# Fysetc_F6_TMC-Shield_HV.net
KiCad netlist of a schematic drawn in EAGLE
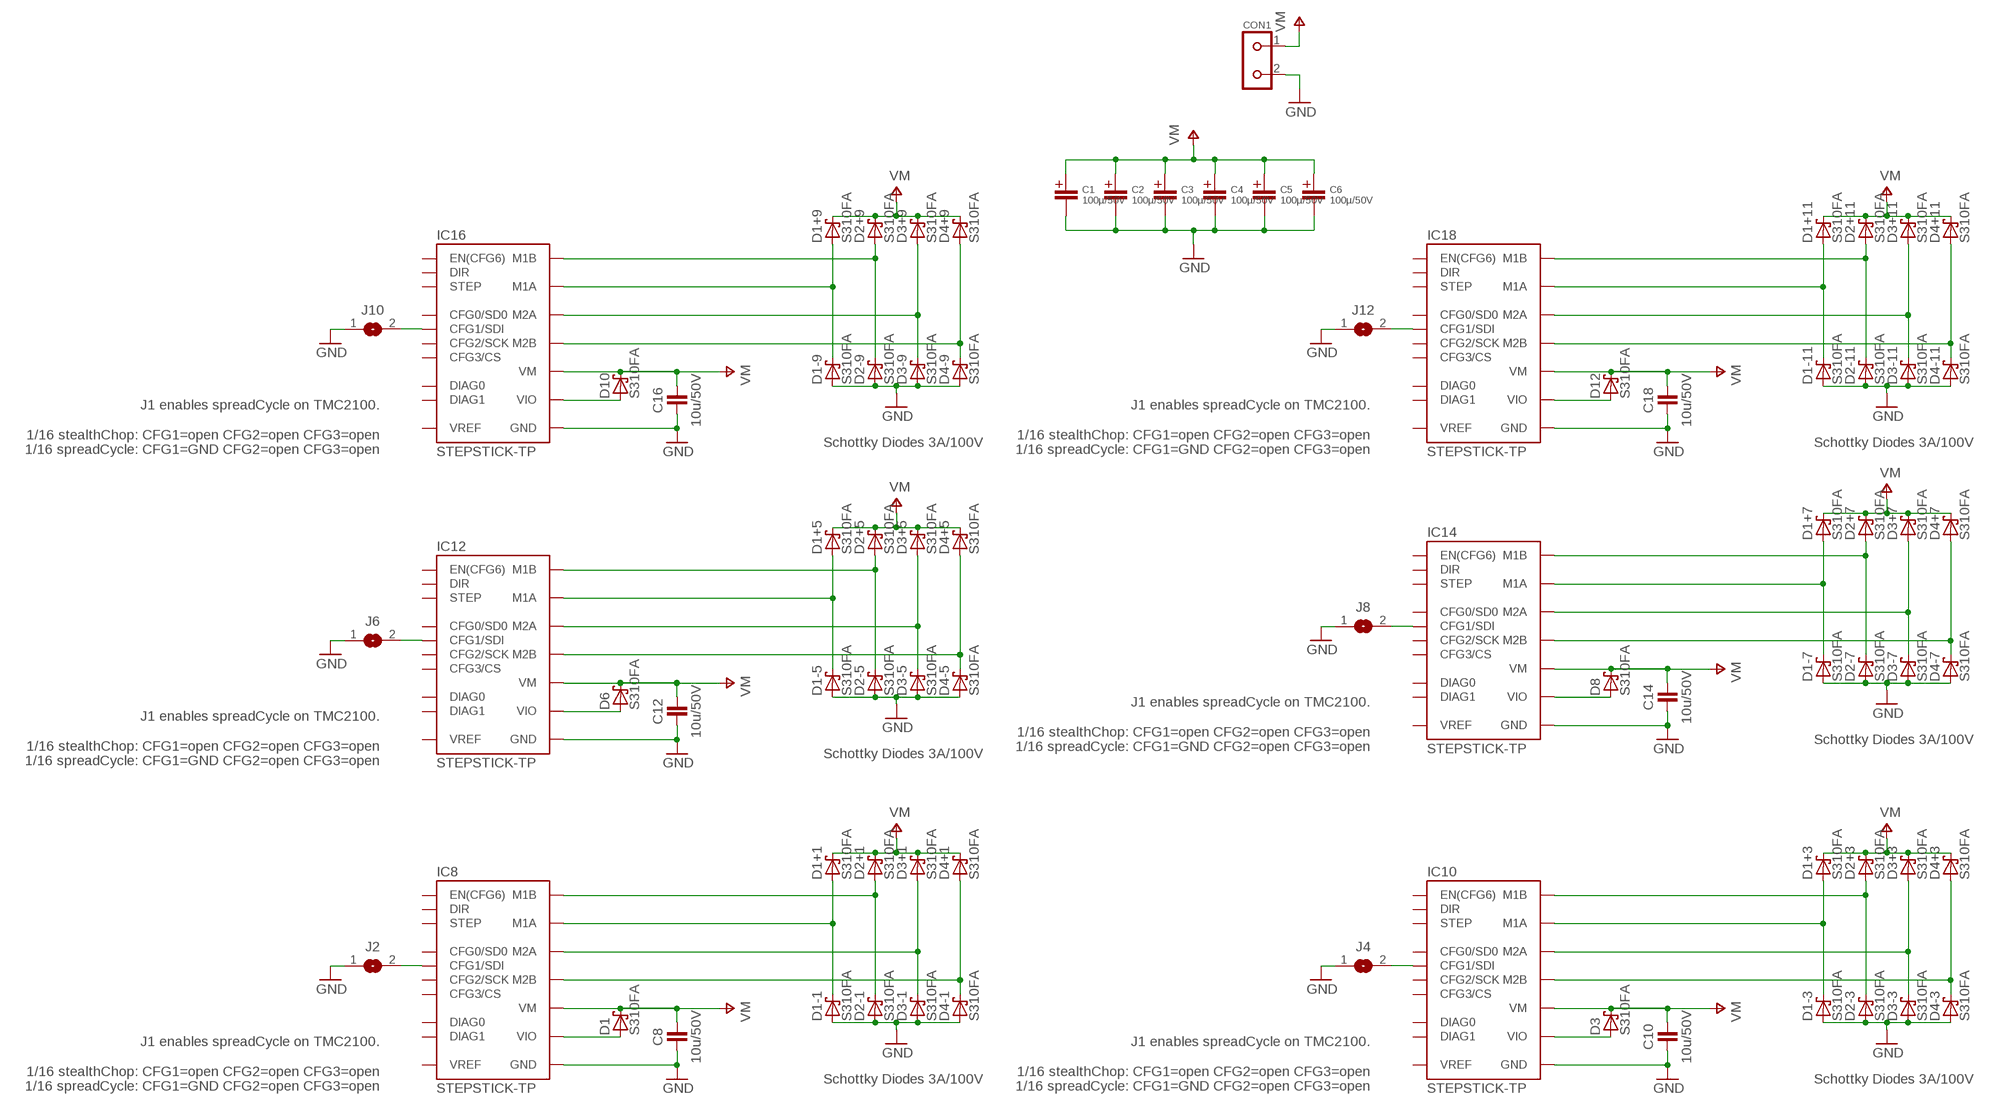
[diagram p0: schematic, sheet 1]

(export (version "E")
  (design (tool "Eeschema 10.0.6"))
  (components
    (comp (ref "C1")
      (value "100µ/50V")
      (footprint "eagle-import:C+_3.5_8")
      (libsource (lib "eagle-import") (part "C+3.5/8"))
    )
    (comp (ref "C2")
      (value "100µ/50V")
      (footprint "eagle-import:C+_3.5_8")
      (libsource (lib "eagle-import") (part "C+3.5/8"))
    )
    (comp (ref "C3")
      (value "100µ/50V")
      (footprint "eagle-import:C+_3.5_8")
      (libsource (lib "eagle-import") (part "C+3.5/8"))
    )
    (comp (ref "C4")
      (value "100µ/50V")
      (footprint "eagle-import:C+_3.5_8")
      (libsource (lib "eagle-import") (part "C+3.5/8"))
    )
    (comp (ref "C5")
      (value "100µ/50V")
      (footprint "eagle-import:C+_3.5_8")
      (libsource (lib "eagle-import") (part "C+3.5/8"))
    )
    (comp (ref "C6")
      (value "100µ/50V")
      (footprint "eagle-import:C+_3.5_8")
      (libsource (lib "eagle-import") (part "C+3.5/8"))
    )
    (comp (ref "C8")
      (value "10u/50V")
      (footprint "eagle-import:C1210")
      (libsource (lib "eagle-import") (part "CAPACITOR-1210"))
    )
    (comp (ref "C10")
      (value "10u/50V")
      (footprint "eagle-import:C1210")
      (libsource (lib "eagle-import") (part "CAPACITOR-1210"))
    )
    (comp (ref "C12")
      (value "10u/50V")
      (footprint "eagle-import:C1210")
      (libsource (lib "eagle-import") (part "CAPACITOR-1210"))
    )
    (comp (ref "C14")
      (value "10u/50V")
      (footprint "eagle-import:C1210")
      (libsource (lib "eagle-import") (part "CAPACITOR-1210"))
    )
    (comp (ref "C16")
      (value "10u/50V")
      (footprint "eagle-import:C1210")
      (libsource (lib "eagle-import") (part "CAPACITOR-1210"))
    )
    (comp (ref "C18")
      (value "10u/50V")
      (footprint "eagle-import:C1210")
      (libsource (lib "eagle-import") (part "CAPACITOR-1210"))
    )
    (comp (ref "CON1")
      (value "KL2691311500002")
      (footprint "eagle-import:KL2-691311500002")
      (libsource (lib "eagle-import") (part "KL2691311500002"))
    )
    (comp (ref "D1")
      (value "S310FA")
      (footprint "eagle-import:SOD123")
      (libsource (lib "eagle-import") (part "D_SCHOTTKY-SOD123"))
    )
    (comp (ref "D1+1")
      (value "S310FA")
      (footprint "eagle-import:SOD123")
      (libsource (lib "eagle-import") (part "D_SCHOTTKY-SOD123"))
    )
    (comp (ref "D1+3")
      (value "S310FA")
      (footprint "eagle-import:SOD123")
      (libsource (lib "eagle-import") (part "D_SCHOTTKY-SOD123"))
    )
    (comp (ref "D1+5")
      (value "S310FA")
      (footprint "eagle-import:SOD123")
      (libsource (lib "eagle-import") (part "D_SCHOTTKY-SOD123"))
    )
    (comp (ref "D1+7")
      (value "S310FA")
      (footprint "eagle-import:SOD123")
      (libsource (lib "eagle-import") (part "D_SCHOTTKY-SOD123"))
    )
    (comp (ref "D1+9")
      (value "S310FA")
      (footprint "eagle-import:SOD123")
      (libsource (lib "eagle-import") (part "D_SCHOTTKY-SOD123"))
    )
    (comp (ref "D1+11")
      (value "S310FA")
      (footprint "eagle-import:SOD123")
      (libsource (lib "eagle-import") (part "D_SCHOTTKY-SOD123"))
    )
    (comp (ref "D1-1")
      (value "S310FA")
      (footprint "eagle-import:SOD123")
      (libsource (lib "eagle-import") (part "D_SCHOTTKY-SOD123"))
    )
    (comp (ref "D1-3")
      (value "S310FA")
      (footprint "eagle-import:SOD123")
      (libsource (lib "eagle-import") (part "D_SCHOTTKY-SOD123"))
    )
    (comp (ref "D1-5")
      (value "S310FA")
      (footprint "eagle-import:SOD123")
      (libsource (lib "eagle-import") (part "D_SCHOTTKY-SOD123"))
    )
    (comp (ref "D1-7")
      (value "S310FA")
      (footprint "eagle-import:SOD123")
      (libsource (lib "eagle-import") (part "D_SCHOTTKY-SOD123"))
    )
    (comp (ref "D1-9")
      (value "S310FA")
      (footprint "eagle-import:SOD123")
      (libsource (lib "eagle-import") (part "D_SCHOTTKY-SOD123"))
    )
    (comp (ref "D1-11")
      (value "S310FA")
      (footprint "eagle-import:SOD123")
      (libsource (lib "eagle-import") (part "D_SCHOTTKY-SOD123"))
    )
    (comp (ref "D2+1")
      (value "S310FA")
      (footprint "eagle-import:SOD123")
      (libsource (lib "eagle-import") (part "D_SCHOTTKY-SOD123"))
    )
    (comp (ref "D2+3")
      (value "S310FA")
      (footprint "eagle-import:SOD123")
      (libsource (lib "eagle-import") (part "D_SCHOTTKY-SOD123"))
    )
    (comp (ref "D2+5")
      (value "S310FA")
      (footprint "eagle-import:SOD123")
      (libsource (lib "eagle-import") (part "D_SCHOTTKY-SOD123"))
    )
    (comp (ref "D2+7")
      (value "S310FA")
      (footprint "eagle-import:SOD123")
      (libsource (lib "eagle-import") (part "D_SCHOTTKY-SOD123"))
    )
    (comp (ref "D2+9")
      (value "S310FA")
      (footprint "eagle-import:SOD123")
      (libsource (lib "eagle-import") (part "D_SCHOTTKY-SOD123"))
    )
    (comp (ref "D2+11")
      (value "S310FA")
      (footprint "eagle-import:SOD123")
      (libsource (lib "eagle-import") (part "D_SCHOTTKY-SOD123"))
    )
    (comp (ref "D2-1")
      (value "S310FA")
      (footprint "eagle-import:SOD123")
      (libsource (lib "eagle-import") (part "D_SCHOTTKY-SOD123"))
    )
    (comp (ref "D2-3")
      (value "S310FA")
      (footprint "eagle-import:SOD123")
      (libsource (lib "eagle-import") (part "D_SCHOTTKY-SOD123"))
    )
    (comp (ref "D2-5")
      (value "S310FA")
      (footprint "eagle-import:SOD123")
      (libsource (lib "eagle-import") (part "D_SCHOTTKY-SOD123"))
    )
    (comp (ref "D2-7")
      (value "S310FA")
      (footprint "eagle-import:SOD123")
      (libsource (lib "eagle-import") (part "D_SCHOTTKY-SOD123"))
    )
    (comp (ref "D2-9")
      (value "S310FA")
      (footprint "eagle-import:SOD123")
      (libsource (lib "eagle-import") (part "D_SCHOTTKY-SOD123"))
    )
    (comp (ref "D2-11")
      (value "S310FA")
      (footprint "eagle-import:SOD123")
      (libsource (lib "eagle-import") (part "D_SCHOTTKY-SOD123"))
    )
    (comp (ref "D3")
      (value "S310FA")
      (footprint "eagle-import:SOD123")
      (libsource (lib "eagle-import") (part "D_SCHOTTKY-SOD123"))
    )
    (comp (ref "D3+1")
      (value "S310FA")
      (footprint "eagle-import:SOD123")
      (libsource (lib "eagle-import") (part "D_SCHOTTKY-SOD123"))
    )
    (comp (ref "D3+3")
      (value "S310FA")
      (footprint "eagle-import:SOD123")
      (libsource (lib "eagle-import") (part "D_SCHOTTKY-SOD123"))
    )
    (comp (ref "D3+5")
      (value "S310FA")
      (footprint "eagle-import:SOD123")
      (libsource (lib "eagle-import") (part "D_SCHOTTKY-SOD123"))
    )
    (comp (ref "D3+7")
      (value "S310FA")
      (footprint "eagle-import:SOD123")
      (libsource (lib "eagle-import") (part "D_SCHOTTKY-SOD123"))
    )
    (comp (ref "D3+9")
      (value "S310FA")
      (footprint "eagle-import:SOD123")
      (libsource (lib "eagle-import") (part "D_SCHOTTKY-SOD123"))
    )
    (comp (ref "D3+11")
      (value "S310FA")
      (footprint "eagle-import:SOD123")
      (libsource (lib "eagle-import") (part "D_SCHOTTKY-SOD123"))
    )
    (comp (ref "D3-1")
      (value "S310FA")
      (footprint "eagle-import:SOD123")
      (libsource (lib "eagle-import") (part "D_SCHOTTKY-SOD123"))
    )
    (comp (ref "D3-3")
      (value "S310FA")
      (footprint "eagle-import:SOD123")
      (libsource (lib "eagle-import") (part "D_SCHOTTKY-SOD123"))
    )
    (comp (ref "D3-5")
      (value "S310FA")
      (footprint "eagle-import:SOD123")
      (libsource (lib "eagle-import") (part "D_SCHOTTKY-SOD123"))
    )
    (comp (ref "D3-7")
      (value "S310FA")
      (footprint "eagle-import:SOD123")
      (libsource (lib "eagle-import") (part "D_SCHOTTKY-SOD123"))
    )
    (comp (ref "D3-9")
      (value "S310FA")
      (footprint "eagle-import:SOD123")
      (libsource (lib "eagle-import") (part "D_SCHOTTKY-SOD123"))
    )
    (comp (ref "D3-11")
      (value "S310FA")
      (footprint "eagle-import:SOD123")
      (libsource (lib "eagle-import") (part "D_SCHOTTKY-SOD123"))
    )
    (comp (ref "D4+1")
      (value "S310FA")
      (footprint "eagle-import:SOD123")
      (libsource (lib "eagle-import") (part "D_SCHOTTKY-SOD123"))
    )
    (comp (ref "D4+3")
      (value "S310FA")
      (footprint "eagle-import:SOD123")
      (libsource (lib "eagle-import") (part "D_SCHOTTKY-SOD123"))
    )
    (comp (ref "D4+5")
      (value "S310FA")
      (footprint "eagle-import:SOD123")
      (libsource (lib "eagle-import") (part "D_SCHOTTKY-SOD123"))
    )
    (comp (ref "D4+7")
      (value "S310FA")
      (footprint "eagle-import:SOD123")
      (libsource (lib "eagle-import") (part "D_SCHOTTKY-SOD123"))
    )
    (comp (ref "D4+9")
      (value "S310FA")
      (footprint "eagle-import:SOD123")
      (libsource (lib "eagle-import") (part "D_SCHOTTKY-SOD123"))
    )
    (comp (ref "D4+11")
      (value "S310FA")
      (footprint "eagle-import:SOD123")
      (libsource (lib "eagle-import") (part "D_SCHOTTKY-SOD123"))
    )
    (comp (ref "D4-1")
      (value "S310FA")
      (footprint "eagle-import:SOD123")
      (libsource (lib "eagle-import") (part "D_SCHOTTKY-SOD123"))
    )
    (comp (ref "D4-3")
      (value "S310FA")
      (footprint "eagle-import:SOD123")
      (libsource (lib "eagle-import") (part "D_SCHOTTKY-SOD123"))
    )
    (comp (ref "D4-5")
      (value "S310FA")
      (footprint "eagle-import:SOD123")
      (libsource (lib "eagle-import") (part "D_SCHOTTKY-SOD123"))
    )
    (comp (ref "D4-7")
      (value "S310FA")
      (footprint "eagle-import:SOD123")
      (libsource (lib "eagle-import") (part "D_SCHOTTKY-SOD123"))
    )
    (comp (ref "D4-9")
      (value "S310FA")
      (footprint "eagle-import:SOD123")
      (libsource (lib "eagle-import") (part "D_SCHOTTKY-SOD123"))
    )
    (comp (ref "D4-11")
      (value "S310FA")
      (footprint "eagle-import:SOD123")
      (libsource (lib "eagle-import") (part "D_SCHOTTKY-SOD123"))
    )
    (comp (ref "D6")
      (value "S310FA")
      (footprint "eagle-import:SOD123")
      (libsource (lib "eagle-import") (part "D_SCHOTTKY-SOD123"))
    )
    (comp (ref "D8")
      (value "S310FA")
      (footprint "eagle-import:SOD123")
      (libsource (lib "eagle-import") (part "D_SCHOTTKY-SOD123"))
    )
    (comp (ref "D10")
      (value "S310FA")
      (footprint "eagle-import:SOD123")
      (libsource (lib "eagle-import") (part "D_SCHOTTKY-SOD123"))
    )
    (comp (ref "D12")
      (value "S310FA")
      (footprint "eagle-import:SOD123")
      (libsource (lib "eagle-import") (part "D_SCHOTTKY-SOD123"))
    )
    (comp (ref "IC8")
      (value "STEPSTICK-TP")
      (footprint "eagle-import:STEPSTICK_TP")
      (libsource (lib "eagle-import") (part "STEPSTICK-TP"))
    )
    (comp (ref "IC10")
      (value "STEPSTICK-TP")
      (footprint "eagle-import:STEPSTICK_TP")
      (libsource (lib "eagle-import") (part "STEPSTICK-TP"))
    )
    (comp (ref "IC12")
      (value "STEPSTICK-TP")
      (footprint "eagle-import:STEPSTICK_TP")
      (libsource (lib "eagle-import") (part "STEPSTICK-TP"))
    )
    (comp (ref "IC14")
      (value "STEPSTICK-TP")
      (footprint "eagle-import:STEPSTICK_TP")
      (libsource (lib "eagle-import") (part "STEPSTICK-TP"))
    )
    (comp (ref "IC16")
      (value "STEPSTICK-TP")
      (footprint "eagle-import:STEPSTICK_TP")
      (libsource (lib "eagle-import") (part "STEPSTICK-TP"))
    )
    (comp (ref "IC18")
      (value "STEPSTICK-TP")
      (footprint "eagle-import:STEPSTICK_TP")
      (libsource (lib "eagle-import") (part "STEPSTICK-TP"))
    )
    (comp (ref "J2")
      (value "JUMPER2-0603-NC")
      (footprint "eagle-import:JUMPER2-0603_NC")
      (libsource (lib "eagle-import") (part "JUMPER2-0603-NC"))
    )
    (comp (ref "J4")
      (value "JUMPER2-0603-NC")
      (footprint "eagle-import:JUMPER2-0603_NC")
      (libsource (lib "eagle-import") (part "JUMPER2-0603-NC"))
    )
    (comp (ref "J6")
      (value "JUMPER2-0603-NC")
      (footprint "eagle-import:JUMPER2-0603_NC")
      (libsource (lib "eagle-import") (part "JUMPER2-0603-NC"))
    )
    (comp (ref "J8")
      (value "JUMPER2-0603-NC")
      (footprint "eagle-import:JUMPER2-0603_NC")
      (libsource (lib "eagle-import") (part "JUMPER2-0603-NC"))
    )
    (comp (ref "J10")
      (value "JUMPER2-0603-NC")
      (footprint "eagle-import:JUMPER2-0603_NC")
      (libsource (lib "eagle-import") (part "JUMPER2-0603-NC"))
    )
    (comp (ref "J12")
      (value "JUMPER2-0603-NC")
      (footprint "eagle-import:JUMPER2-0603_NC")
      (libsource (lib "eagle-import") (part "JUMPER2-0603-NC"))
    )
  )
  (nets
    (net (code "1") (name "GND") (class "Default")
      (node (ref "C1") (pin "-") (pinfunction "-_-") (pintype "passive"))
      (node (ref "C10") (pin "1") (pinfunction "1_1") (pintype "passive"))
      (node (ref "C12") (pin "1") (pinfunction "1_1") (pintype "passive"))
      (node (ref "C14") (pin "1") (pinfunction "1_1") (pintype "passive"))
      (node (ref "C16") (pin "1") (pinfunction "1_1") (pintype "passive"))
      (node (ref "C18") (pin "1") (pinfunction "1_1") (pintype "passive"))
      (node (ref "C2") (pin "-") (pinfunction "-_-") (pintype "passive"))
      (node (ref "C3") (pin "-") (pinfunction "-_-") (pintype "passive"))
      (node (ref "C4") (pin "-") (pinfunction "-_-") (pintype "passive"))
      (node (ref "C5") (pin "-") (pinfunction "-_-") (pintype "passive"))
      (node (ref "C6") (pin "-") (pinfunction "-_-") (pintype "passive"))
      (node (ref "C8") (pin "1") (pinfunction "1_1") (pintype "passive"))
      (node (ref "CON1") (pin "2") (pinfunction "2_2") (pintype "passive"))
      (node (ref "D1-1") (pin "A") (pinfunction "A_A") (pintype "passive"))
      (node (ref "D1-11") (pin "A") (pinfunction "A_A") (pintype "passive"))
      (node (ref "D1-3") (pin "A") (pinfunction "A_A") (pintype "passive"))
      (node (ref "D1-5") (pin "A") (pinfunction "A_A") (pintype "passive"))
      (node (ref "D1-7") (pin "A") (pinfunction "A_A") (pintype "passive"))
      (node (ref "D1-9") (pin "A") (pinfunction "A_A") (pintype "passive"))
      (node (ref "D2-1") (pin "A") (pinfunction "A_A") (pintype "passive"))
      (node (ref "D2-11") (pin "A") (pinfunction "A_A") (pintype "passive"))
      (node (ref "D2-3") (pin "A") (pinfunction "A_A") (pintype "passive"))
      (node (ref "D2-5") (pin "A") (pinfunction "A_A") (pintype "passive"))
      (node (ref "D2-7") (pin "A") (pinfunction "A_A") (pintype "passive"))
      (node (ref "D2-9") (pin "A") (pinfunction "A_A") (pintype "passive"))
      (node (ref "D3-1") (pin "A") (pinfunction "A_A") (pintype "passive"))
      (node (ref "D3-11") (pin "A") (pinfunction "A_A") (pintype "passive"))
      (node (ref "D3-3") (pin "A") (pinfunction "A_A") (pintype "passive"))
      (node (ref "D3-5") (pin "A") (pinfunction "A_A") (pintype "passive"))
      (node (ref "D3-7") (pin "A") (pinfunction "A_A") (pintype "passive"))
      (node (ref "D3-9") (pin "A") (pinfunction "A_A") (pintype "passive"))
      (node (ref "D4-1") (pin "A") (pinfunction "A_A") (pintype "passive"))
      (node (ref "D4-11") (pin "A") (pinfunction "A_A") (pintype "passive"))
      (node (ref "D4-3") (pin "A") (pinfunction "A_A") (pintype "passive"))
      (node (ref "D4-5") (pin "A") (pinfunction "A_A") (pintype "passive"))
      (node (ref "D4-7") (pin "A") (pinfunction "A_A") (pintype "passive"))
      (node (ref "D4-9") (pin "A") (pinfunction "A_A") (pintype "passive"))
      (node (ref "IC10") (pin "GND@1") (pinfunction "GND_GND@1") (pintype "power_in"))
      (node (ref "IC10") (pin "GND@2") (pinfunction "GND_GND@2") (pintype "power_in"))
      (node (ref "IC12") (pin "GND@1") (pinfunction "GND_GND@1") (pintype "power_in"))
      (node (ref "IC12") (pin "GND@2") (pinfunction "GND_GND@2") (pintype "power_in"))
      (node (ref "IC14") (pin "GND@1") (pinfunction "GND_GND@1") (pintype "power_in"))
      (node (ref "IC14") (pin "GND@2") (pinfunction "GND_GND@2") (pintype "power_in"))
      (node (ref "IC16") (pin "GND@1") (pinfunction "GND_GND@1") (pintype "power_in"))
      (node (ref "IC16") (pin "GND@2") (pinfunction "GND_GND@2") (pintype "power_in"))
      (node (ref "IC18") (pin "GND@1") (pinfunction "GND_GND@1") (pintype "power_in"))
      (node (ref "IC18") (pin "GND@2") (pinfunction "GND_GND@2") (pintype "power_in"))
      (node (ref "IC8") (pin "GND@1") (pinfunction "GND_GND@1") (pintype "power_in"))
      (node (ref "IC8") (pin "GND@2") (pinfunction "GND_GND@2") (pintype "power_in"))
      (node (ref "J10") (pin "1") (pinfunction "1_1") (pintype "passive"))
      (node (ref "J12") (pin "1") (pinfunction "1_1") (pintype "passive"))
      (node (ref "J2") (pin "1") (pinfunction "1_1") (pintype "passive"))
      (node (ref "J4") (pin "1") (pinfunction "1_1") (pintype "passive"))
      (node (ref "J6") (pin "1") (pinfunction "1_1") (pintype "passive"))
      (node (ref "J8") (pin "1") (pinfunction "1_1") (pintype "passive"))
    )
    (net (code "2") (name "Net-(D1+1-PadA)") (class "Default")
      (node (ref "D1+1") (pin "A") (pinfunction "A_A") (pintype "passive"))
      (node (ref "D1-1") (pin "C") (pinfunction "C_C") (pintype "passive"))
      (node (ref "IC8") (pin "M1A") (pinfunction "M1A_M1A") (pintype "output"))
    )
    (net (code "3") (name "Net-(D1+3-PadA)") (class "Default")
      (node (ref "D1+3") (pin "A") (pinfunction "A_A") (pintype "passive"))
      (node (ref "D1-3") (pin "C") (pinfunction "C_C") (pintype "passive"))
      (node (ref "IC10") (pin "M1A") (pinfunction "M1A_M1A") (pintype "output"))
    )
    (net (code "4") (name "Net-(D1+5-PadA)") (class "Default")
      (node (ref "D1+5") (pin "A") (pinfunction "A_A") (pintype "passive"))
      (node (ref "D1-5") (pin "C") (pinfunction "C_C") (pintype "passive"))
      (node (ref "IC12") (pin "M1A") (pinfunction "M1A_M1A") (pintype "output"))
    )
    (net (code "5") (name "Net-(D1+7-PadA)") (class "Default")
      (node (ref "D1+7") (pin "A") (pinfunction "A_A") (pintype "passive"))
      (node (ref "D1-7") (pin "C") (pinfunction "C_C") (pintype "passive"))
      (node (ref "IC14") (pin "M1A") (pinfunction "M1A_M1A") (pintype "output"))
    )
    (net (code "6") (name "Net-(D1+9-PadA)") (class "Default")
      (node (ref "D1+9") (pin "A") (pinfunction "A_A") (pintype "passive"))
      (node (ref "D1-9") (pin "C") (pinfunction "C_C") (pintype "passive"))
      (node (ref "IC16") (pin "M1A") (pinfunction "M1A_M1A") (pintype "output"))
    )
    (net (code "7") (name "Net-(D1+11-PadA)") (class "Default")
      (node (ref "D1+11") (pin "A") (pinfunction "A_A") (pintype "passive"))
      (node (ref "D1-11") (pin "C") (pinfunction "C_C") (pintype "passive"))
      (node (ref "IC18") (pin "M1A") (pinfunction "M1A_M1A") (pintype "output"))
    )
    (net (code "8") (name "Net-(D1-PadA)") (class "Default")
      (node (ref "D1") (pin "A") (pinfunction "A_A") (pintype "passive"))
      (node (ref "IC8") (pin "VIO") (pinfunction "VIO_VIO") (pintype "power_in"))
    )
    (net (code "9") (name "Net-(D2+1-PadA)") (class "Default")
      (node (ref "D2+1") (pin "A") (pinfunction "A_A") (pintype "passive"))
      (node (ref "D2-1") (pin "C") (pinfunction "C_C") (pintype "passive"))
      (node (ref "IC8") (pin "M1B") (pinfunction "M1B_M1B") (pintype "output"))
    )
    (net (code "10") (name "Net-(D2+3-PadA)") (class "Default")
      (node (ref "D2+3") (pin "A") (pinfunction "A_A") (pintype "passive"))
      (node (ref "D2-3") (pin "C") (pinfunction "C_C") (pintype "passive"))
      (node (ref "IC10") (pin "M1B") (pinfunction "M1B_M1B") (pintype "output"))
    )
    (net (code "11") (name "Net-(D2+5-PadA)") (class "Default")
      (node (ref "D2+5") (pin "A") (pinfunction "A_A") (pintype "passive"))
      (node (ref "D2-5") (pin "C") (pinfunction "C_C") (pintype "passive"))
      (node (ref "IC12") (pin "M1B") (pinfunction "M1B_M1B") (pintype "output"))
    )
    (net (code "12") (name "Net-(D2+7-PadA)") (class "Default")
      (node (ref "D2+7") (pin "A") (pinfunction "A_A") (pintype "passive"))
      (node (ref "D2-7") (pin "C") (pinfunction "C_C") (pintype "passive"))
      (node (ref "IC14") (pin "M1B") (pinfunction "M1B_M1B") (pintype "output"))
    )
    (net (code "13") (name "Net-(D2+9-PadA)") (class "Default")
      (node (ref "D2+9") (pin "A") (pinfunction "A_A") (pintype "passive"))
      (node (ref "D2-9") (pin "C") (pinfunction "C_C") (pintype "passive"))
      (node (ref "IC16") (pin "M1B") (pinfunction "M1B_M1B") (pintype "output"))
    )
    (net (code "14") (name "Net-(D2+11-PadA)") (class "Default")
      (node (ref "D2+11") (pin "A") (pinfunction "A_A") (pintype "passive"))
      (node (ref "D2-11") (pin "C") (pinfunction "C_C") (pintype "passive"))
      (node (ref "IC18") (pin "M1B") (pinfunction "M1B_M1B") (pintype "output"))
    )
    (net (code "15") (name "Net-(D3+1-PadA)") (class "Default")
      (node (ref "D3+1") (pin "A") (pinfunction "A_A") (pintype "passive"))
      (node (ref "D3-1") (pin "C") (pinfunction "C_C") (pintype "passive"))
      (node (ref "IC8") (pin "M2A") (pinfunction "M2A_M2A") (pintype "output"))
    )
    (net (code "16") (name "Net-(D3+3-PadA)") (class "Default")
      (node (ref "D3+3") (pin "A") (pinfunction "A_A") (pintype "passive"))
      (node (ref "D3-3") (pin "C") (pinfunction "C_C") (pintype "passive"))
      (node (ref "IC10") (pin "M2A") (pinfunction "M2A_M2A") (pintype "output"))
    )
    (net (code "17") (name "Net-(D3+5-PadA)") (class "Default")
      (node (ref "D3+5") (pin "A") (pinfunction "A_A") (pintype "passive"))
      (node (ref "D3-5") (pin "C") (pinfunction "C_C") (pintype "passive"))
      (node (ref "IC12") (pin "M2A") (pinfunction "M2A_M2A") (pintype "output"))
    )
    (net (code "18") (name "Net-(D3+7-PadA)") (class "Default")
      (node (ref "D3+7") (pin "A") (pinfunction "A_A") (pintype "passive"))
      (node (ref "D3-7") (pin "C") (pinfunction "C_C") (pintype "passive"))
      (node (ref "IC14") (pin "M2A") (pinfunction "M2A_M2A") (pintype "output"))
    )
    (net (code "19") (name "Net-(D3+9-PadA)") (class "Default")
      (node (ref "D3+9") (pin "A") (pinfunction "A_A") (pintype "passive"))
      (node (ref "D3-9") (pin "C") (pinfunction "C_C") (pintype "passive"))
      (node (ref "IC16") (pin "M2A") (pinfunction "M2A_M2A") (pintype "output"))
    )
    (net (code "20") (name "Net-(D3+11-PadA)") (class "Default")
      (node (ref "D3+11") (pin "A") (pinfunction "A_A") (pintype "passive"))
      (node (ref "D3-11") (pin "C") (pinfunction "C_C") (pintype "passive"))
      (node (ref "IC18") (pin "M2A") (pinfunction "M2A_M2A") (pintype "output"))
    )
    (net (code "21") (name "Net-(D3-PadA)") (class "Default")
      (node (ref "D3") (pin "A") (pinfunction "A_A") (pintype "passive"))
      (node (ref "IC10") (pin "VIO") (pinfunction "VIO_VIO") (pintype "power_in"))
    )
    (net (code "22") (name "Net-(D4+1-PadA)") (class "Default")
      (node (ref "D4+1") (pin "A") (pinfunction "A_A") (pintype "passive"))
      (node (ref "D4-1") (pin "C") (pinfunction "C_C") (pintype "passive"))
      (node (ref "IC8") (pin "M2B") (pinfunction "M2B_M2B") (pintype "output"))
    )
    (net (code "23") (name "Net-(D4+3-PadA)") (class "Default")
      (node (ref "D4+3") (pin "A") (pinfunction "A_A") (pintype "passive"))
      (node (ref "D4-3") (pin "C") (pinfunction "C_C") (pintype "passive"))
      (node (ref "IC10") (pin "M2B") (pinfunction "M2B_M2B") (pintype "output"))
    )
    (net (code "24") (name "Net-(D4+5-PadA)") (class "Default")
      (node (ref "D4+5") (pin "A") (pinfunction "A_A") (pintype "passive"))
      (node (ref "D4-5") (pin "C") (pinfunction "C_C") (pintype "passive"))
      (node (ref "IC12") (pin "M2B") (pinfunction "M2B_M2B") (pintype "output"))
    )
    (net (code "25") (name "Net-(D4+7-PadA)") (class "Default")
      (node (ref "D4+7") (pin "A") (pinfunction "A_A") (pintype "passive"))
      (node (ref "D4-7") (pin "C") (pinfunction "C_C") (pintype "passive"))
      (node (ref "IC14") (pin "M2B") (pinfunction "M2B_M2B") (pintype "output"))
    )
    (net (code "26") (name "Net-(D4+9-PadA)") (class "Default")
      (node (ref "D4+9") (pin "A") (pinfunction "A_A") (pintype "passive"))
      (node (ref "D4-9") (pin "C") (pinfunction "C_C") (pintype "passive"))
      (node (ref "IC16") (pin "M2B") (pinfunction "M2B_M2B") (pintype "output"))
    )
    (net (code "27") (name "Net-(D4+11-PadA)") (class "Default")
      (node (ref "D4+11") (pin "A") (pinfunction "A_A") (pintype "passive"))
      (node (ref "D4-11") (pin "C") (pinfunction "C_C") (pintype "passive"))
      (node (ref "IC18") (pin "M2B") (pinfunction "M2B_M2B") (pintype "output"))
    )
    (net (code "28") (name "Net-(D6-PadA)") (class "Default")
      (node (ref "D6") (pin "A") (pinfunction "A_A") (pintype "passive"))
      (node (ref "IC12") (pin "VIO") (pinfunction "VIO_VIO") (pintype "power_in"))
    )
    (net (code "29") (name "Net-(D8-PadA)") (class "Default")
      (node (ref "D8") (pin "A") (pinfunction "A_A") (pintype "passive"))
      (node (ref "IC14") (pin "VIO") (pinfunction "VIO_VIO") (pintype "power_in"))
    )
    (net (code "30") (name "Net-(D10-PadA)") (class "Default")
      (node (ref "D10") (pin "A") (pinfunction "A_A") (pintype "passive"))
      (node (ref "IC16") (pin "VIO") (pinfunction "VIO_VIO") (pintype "power_in"))
    )
    (net (code "31") (name "Net-(D12-PadA)") (class "Default")
      (node (ref "D12") (pin "A") (pinfunction "A_A") (pintype "passive"))
      (node (ref "IC18") (pin "VIO") (pinfunction "VIO_VIO") (pintype "power_in"))
    )
    (net (code "32") (name "Net-(IC8-CFG1{slash}SDI)") (class "Default")
      (node (ref "IC8") (pin "CFG1") (pinfunction "CFG1/SDI_CFG1") (pintype "bidirectional"))
      (node (ref "J2") (pin "2") (pinfunction "2_2") (pintype "passive"))
    )
    (net (code "33") (name "Net-(IC10-CFG1{slash}SDI)") (class "Default")
      (node (ref "IC10") (pin "CFG1") (pinfunction "CFG1/SDI_CFG1") (pintype "bidirectional"))
      (node (ref "J4") (pin "2") (pinfunction "2_2") (pintype "passive"))
    )
    (net (code "34") (name "Net-(IC12-CFG1{slash}SDI)") (class "Default")
      (node (ref "IC12") (pin "CFG1") (pinfunction "CFG1/SDI_CFG1") (pintype "bidirectional"))
      (node (ref "J6") (pin "2") (pinfunction "2_2") (pintype "passive"))
    )
    (net (code "35") (name "Net-(IC14-CFG1{slash}SDI)") (class "Default")
      (node (ref "IC14") (pin "CFG1") (pinfunction "CFG1/SDI_CFG1") (pintype "bidirectional"))
      (node (ref "J8") (pin "2") (pinfunction "2_2") (pintype "passive"))
    )
    (net (code "36") (name "Net-(IC16-CFG1{slash}SDI)") (class "Default")
      (node (ref "IC16") (pin "CFG1") (pinfunction "CFG1/SDI_CFG1") (pintype "bidirectional"))
      (node (ref "J10") (pin "2") (pinfunction "2_2") (pintype "passive"))
    )
    (net (code "37") (name "Net-(IC18-CFG1{slash}SDI)") (class "Default")
      (node (ref "IC18") (pin "CFG1") (pinfunction "CFG1/SDI_CFG1") (pintype "bidirectional"))
      (node (ref "J12") (pin "2") (pinfunction "2_2") (pintype "passive"))
    )
    (net (code "38") (name "VM") (class "Default")
      (node (ref "C1") (pin "+") (pinfunction "+_+") (pintype "passive"))
      (node (ref "C10") (pin "2") (pinfunction "2_2") (pintype "passive"))
      (node (ref "C12") (pin "2") (pinfunction "2_2") (pintype "passive"))
      (node (ref "C14") (pin "2") (pinfunction "2_2") (pintype "passive"))
      (node (ref "C16") (pin "2") (pinfunction "2_2") (pintype "passive"))
      (node (ref "C18") (pin "2") (pinfunction "2_2") (pintype "passive"))
      (node (ref "C2") (pin "+") (pinfunction "+_+") (pintype "passive"))
      (node (ref "C3") (pin "+") (pinfunction "+_+") (pintype "passive"))
      (node (ref "C4") (pin "+") (pinfunction "+_+") (pintype "passive"))
      (node (ref "C5") (pin "+") (pinfunction "+_+") (pintype "passive"))
      (node (ref "C6") (pin "+") (pinfunction "+_+") (pintype "passive"))
      (node (ref "C8") (pin "2") (pinfunction "2_2") (pintype "passive"))
      (node (ref "CON1") (pin "1") (pinfunction "1_1") (pintype "passive"))
      (node (ref "D1") (pin "C") (pinfunction "C_C") (pintype "passive"))
      (node (ref "D1+1") (pin "C") (pinfunction "C_C") (pintype "passive"))
      (node (ref "D1+11") (pin "C") (pinfunction "C_C") (pintype "passive"))
      (node (ref "D1+3") (pin "C") (pinfunction "C_C") (pintype "passive"))
      (node (ref "D1+5") (pin "C") (pinfunction "C_C") (pintype "passive"))
      (node (ref "D1+7") (pin "C") (pinfunction "C_C") (pintype "passive"))
      (node (ref "D1+9") (pin "C") (pinfunction "C_C") (pintype "passive"))
      (node (ref "D10") (pin "C") (pinfunction "C_C") (pintype "passive"))
      (node (ref "D12") (pin "C") (pinfunction "C_C") (pintype "passive"))
      (node (ref "D2+1") (pin "C") (pinfunction "C_C") (pintype "passive"))
      (node (ref "D2+11") (pin "C") (pinfunction "C_C") (pintype "passive"))
      (node (ref "D2+3") (pin "C") (pinfunction "C_C") (pintype "passive"))
      (node (ref "D2+5") (pin "C") (pinfunction "C_C") (pintype "passive"))
      (node (ref "D2+7") (pin "C") (pinfunction "C_C") (pintype "passive"))
      (node (ref "D2+9") (pin "C") (pinfunction "C_C") (pintype "passive"))
      (node (ref "D3") (pin "C") (pinfunction "C_C") (pintype "passive"))
      (node (ref "D3+1") (pin "C") (pinfunction "C_C") (pintype "passive"))
      (node (ref "D3+11") (pin "C") (pinfunction "C_C") (pintype "passive"))
      (node (ref "D3+3") (pin "C") (pinfunction "C_C") (pintype "passive"))
      (node (ref "D3+5") (pin "C") (pinfunction "C_C") (pintype "passive"))
      (node (ref "D3+7") (pin "C") (pinfunction "C_C") (pintype "passive"))
      (node (ref "D3+9") (pin "C") (pinfunction "C_C") (pintype "passive"))
      (node (ref "D4+1") (pin "C") (pinfunction "C_C") (pintype "passive"))
      (node (ref "D4+11") (pin "C") (pinfunction "C_C") (pintype "passive"))
      (node (ref "D4+3") (pin "C") (pinfunction "C_C") (pintype "passive"))
      (node (ref "D4+5") (pin "C") (pinfunction "C_C") (pintype "passive"))
      (node (ref "D4+7") (pin "C") (pinfunction "C_C") (pintype "passive"))
      (node (ref "D4+9") (pin "C") (pinfunction "C_C") (pintype "passive"))
      (node (ref "D6") (pin "C") (pinfunction "C_C") (pintype "passive"))
      (node (ref "D8") (pin "C") (pinfunction "C_C") (pintype "passive"))
      (node (ref "IC10") (pin "VM") (pinfunction "VM_VM") (pintype "power_in"))
      (node (ref "IC12") (pin "VM") (pinfunction "VM_VM") (pintype "power_in"))
      (node (ref "IC14") (pin "VM") (pinfunction "VM_VM") (pintype "power_in"))
      (node (ref "IC16") (pin "VM") (pinfunction "VM_VM") (pintype "power_in"))
      (node (ref "IC18") (pin "VM") (pinfunction "VM_VM") (pintype "power_in"))
      (node (ref "IC8") (pin "VM") (pinfunction "VM_VM") (pintype "power_in"))
    )
    (net (code "39") (name "unconnected-(IC8-CFG0{slash}SD0-PadNC{slash}CFG0)") (class "Default")
      (node (ref "IC8") (pin "NC/CFG0") (pinfunction "CFG0/SD0_NC/CFG0") (pintype "bidirectional"))
    )
    (net (code "40") (name "unconnected-(IC8-CFG2{slash}SCK-PadCFG2)") (class "Default")
      (node (ref "IC8") (pin "CFG2") (pinfunction "CFG2/SCK_CFG2") (pintype "bidirectional"))
    )
    (net (code "41") (name "unconnected-(IC8-CFG3{slash}CS-PadCFG3)") (class "Default")
      (node (ref "IC8") (pin "CFG3") (pinfunction "CFG3/CS_CFG3") (pintype "bidirectional"))
    )
    (net (code "42") (name "unconnected-(IC8-EN(CFG6)-PadEN)") (class "Default")
      (node (ref "IC8") (pin "EN") (pinfunction "EN(CFG6)_EN") (pintype "bidirectional"))
    )
    (net (code "43") (name "unconnected-(IC8-PadDIAG0)") (class "Default")
      (node (ref "IC8") (pin "DIAG0") (pinfunction "DIAG0_DIAG0") (pintype "bidirectional"))
    )
    (net (code "44") (name "unconnected-(IC8-PadDIAG1)") (class "Default")
      (node (ref "IC8") (pin "DIAG1") (pinfunction "DIAG1_DIAG1") (pintype "bidirectional"))
    )
    (net (code "45") (name "unconnected-(IC8-PadDIR)") (class "Default")
      (node (ref "IC8") (pin "DIR") (pinfunction "DIR_DIR") (pintype "bidirectional"))
    )
    (net (code "46") (name "unconnected-(IC8-PadSTEP)") (class "Default")
      (node (ref "IC8") (pin "STEP") (pinfunction "STEP_STEP") (pintype "bidirectional"))
    )
    (net (code "47") (name "unconnected-(IC8-PadVREF)") (class "Default")
      (node (ref "IC8") (pin "VREF") (pinfunction "VREF_VREF") (pintype "passive"))
    )
    (net (code "48") (name "unconnected-(IC10-CFG0{slash}SD0-PadNC{slash}CFG0)") (class "Default")
      (node (ref "IC10") (pin "NC/CFG0") (pinfunction "CFG0/SD0_NC/CFG0") (pintype "bidirectional"))
    )
    (net (code "49") (name "unconnected-(IC10-CFG2{slash}SCK-PadCFG2)") (class "Default")
      (node (ref "IC10") (pin "CFG2") (pinfunction "CFG2/SCK_CFG2") (pintype "bidirectional"))
    )
    (net (code "50") (name "unconnected-(IC10-CFG3{slash}CS-PadCFG3)") (class "Default")
      (node (ref "IC10") (pin "CFG3") (pinfunction "CFG3/CS_CFG3") (pintype "bidirectional"))
    )
    (net (code "51") (name "unconnected-(IC10-EN(CFG6)-PadEN)") (class "Default")
      (node (ref "IC10") (pin "EN") (pinfunction "EN(CFG6)_EN") (pintype "bidirectional"))
    )
    (net (code "52") (name "unconnected-(IC10-PadDIAG0)") (class "Default")
      (node (ref "IC10") (pin "DIAG0") (pinfunction "DIAG0_DIAG0") (pintype "bidirectional"))
    )
    (net (code "53") (name "unconnected-(IC10-PadDIAG1)") (class "Default")
      (node (ref "IC10") (pin "DIAG1") (pinfunction "DIAG1_DIAG1") (pintype "bidirectional"))
    )
    (net (code "54") (name "unconnected-(IC10-PadDIR)") (class "Default")
      (node (ref "IC10") (pin "DIR") (pinfunction "DIR_DIR") (pintype "bidirectional"))
    )
    (net (code "55") (name "unconnected-(IC10-PadSTEP)") (class "Default")
      (node (ref "IC10") (pin "STEP") (pinfunction "STEP_STEP") (pintype "bidirectional"))
    )
    (net (code "56") (name "unconnected-(IC10-PadVREF)") (class "Default")
      (node (ref "IC10") (pin "VREF") (pinfunction "VREF_VREF") (pintype "passive"))
    )
    (net (code "57") (name "unconnected-(IC12-CFG0{slash}SD0-PadNC{slash}CFG0)") (class "Default")
      (node (ref "IC12") (pin "NC/CFG0") (pinfunction "CFG0/SD0_NC/CFG0") (pintype "bidirectional"))
    )
    (net (code "58") (name "unconnected-(IC12-CFG2{slash}SCK-PadCFG2)") (class "Default")
      (node (ref "IC12") (pin "CFG2") (pinfunction "CFG2/SCK_CFG2") (pintype "bidirectional"))
    )
    (net (code "59") (name "unconnected-(IC12-CFG3{slash}CS-PadCFG3)") (class "Default")
      (node (ref "IC12") (pin "CFG3") (pinfunction "CFG3/CS_CFG3") (pintype "bidirectional"))
    )
    (net (code "60") (name "unconnected-(IC12-EN(CFG6)-PadEN)") (class "Default")
      (node (ref "IC12") (pin "EN") (pinfunction "EN(CFG6)_EN") (pintype "bidirectional"))
    )
    (net (code "61") (name "unconnected-(IC12-PadDIAG0)") (class "Default")
      (node (ref "IC12") (pin "DIAG0") (pinfunction "DIAG0_DIAG0") (pintype "bidirectional"))
    )
    (net (code "62") (name "unconnected-(IC12-PadDIAG1)") (class "Default")
      (node (ref "IC12") (pin "DIAG1") (pinfunction "DIAG1_DIAG1") (pintype "bidirectional"))
    )
    (net (code "63") (name "unconnected-(IC12-PadDIR)") (class "Default")
      (node (ref "IC12") (pin "DIR") (pinfunction "DIR_DIR") (pintype "bidirectional"))
    )
    (net (code "64") (name "unconnected-(IC12-PadSTEP)") (class "Default")
      (node (ref "IC12") (pin "STEP") (pinfunction "STEP_STEP") (pintype "bidirectional"))
    )
    (net (code "65") (name "unconnected-(IC12-PadVREF)") (class "Default")
      (node (ref "IC12") (pin "VREF") (pinfunction "VREF_VREF") (pintype "passive"))
    )
    (net (code "66") (name "unconnected-(IC14-CFG0{slash}SD0-PadNC{slash}CFG0)") (class "Default")
      (node (ref "IC14") (pin "NC/CFG0") (pinfunction "CFG0/SD0_NC/CFG0") (pintype "bidirectional"))
    )
    (net (code "67") (name "unconnected-(IC14-CFG2{slash}SCK-PadCFG2)") (class "Default")
      (node (ref "IC14") (pin "CFG2") (pinfunction "CFG2/SCK_CFG2") (pintype "bidirectional"))
    )
    (net (code "68") (name "unconnected-(IC14-CFG3{slash}CS-PadCFG3)") (class "Default")
      (node (ref "IC14") (pin "CFG3") (pinfunction "CFG3/CS_CFG3") (pintype "bidirectional"))
    )
    (net (code "69") (name "unconnected-(IC14-EN(CFG6)-PadEN)") (class "Default")
      (node (ref "IC14") (pin "EN") (pinfunction "EN(CFG6)_EN") (pintype "bidirectional"))
    )
    (net (code "70") (name "unconnected-(IC14-PadDIAG0)") (class "Default")
      (node (ref "IC14") (pin "DIAG0") (pinfunction "DIAG0_DIAG0") (pintype "bidirectional"))
    )
    (net (code "71") (name "unconnected-(IC14-PadDIAG1)") (class "Default")
      (node (ref "IC14") (pin "DIAG1") (pinfunction "DIAG1_DIAG1") (pintype "bidirectional"))
    )
    (net (code "72") (name "unconnected-(IC14-PadDIR)") (class "Default")
      (node (ref "IC14") (pin "DIR") (pinfunction "DIR_DIR") (pintype "bidirectional"))
    )
    (net (code "73") (name "unconnected-(IC14-PadSTEP)") (class "Default")
      (node (ref "IC14") (pin "STEP") (pinfunction "STEP_STEP") (pintype "bidirectional"))
    )
    (net (code "74") (name "unconnected-(IC14-PadVREF)") (class "Default")
      (node (ref "IC14") (pin "VREF") (pinfunction "VREF_VREF") (pintype "passive"))
    )
    (net (code "75") (name "unconnected-(IC16-CFG0{slash}SD0-PadNC{slash}CFG0)") (class "Default")
      (node (ref "IC16") (pin "NC/CFG0") (pinfunction "CFG0/SD0_NC/CFG0") (pintype "bidirectional"))
    )
    (net (code "76") (name "unconnected-(IC16-CFG2{slash}SCK-PadCFG2)") (class "Default")
      (node (ref "IC16") (pin "CFG2") (pinfunction "CFG2/SCK_CFG2") (pintype "bidirectional"))
    )
    (net (code "77") (name "unconnected-(IC16-CFG3{slash}CS-PadCFG3)") (class "Default")
      (node (ref "IC16") (pin "CFG3") (pinfunction "CFG3/CS_CFG3") (pintype "bidirectional"))
    )
    (net (code "78") (name "unconnected-(IC16-EN(CFG6)-PadEN)") (class "Default")
      (node (ref "IC16") (pin "EN") (pinfunction "EN(CFG6)_EN") (pintype "bidirectional"))
    )
    (net (code "79") (name "unconnected-(IC16-PadDIAG0)") (class "Default")
      (node (ref "IC16") (pin "DIAG0") (pinfunction "DIAG0_DIAG0") (pintype "bidirectional"))
    )
    (net (code "80") (name "unconnected-(IC16-PadDIAG1)") (class "Default")
      (node (ref "IC16") (pin "DIAG1") (pinfunction "DIAG1_DIAG1") (pintype "bidirectional"))
    )
    (net (code "81") (name "unconnected-(IC16-PadDIR)") (class "Default")
      (node (ref "IC16") (pin "DIR") (pinfunction "DIR_DIR") (pintype "bidirectional"))
    )
    (net (code "82") (name "unconnected-(IC16-PadSTEP)") (class "Default")
      (node (ref "IC16") (pin "STEP") (pinfunction "STEP_STEP") (pintype "bidirectional"))
    )
    (net (code "83") (name "unconnected-(IC16-PadVREF)") (class "Default")
      (node (ref "IC16") (pin "VREF") (pinfunction "VREF_VREF") (pintype "passive"))
    )
    (net (code "84") (name "unconnected-(IC18-CFG0{slash}SD0-PadNC{slash}CFG0)") (class "Default")
      (node (ref "IC18") (pin "NC/CFG0") (pinfunction "CFG0/SD0_NC/CFG0") (pintype "bidirectional"))
    )
    (net (code "85") (name "unconnected-(IC18-CFG2{slash}SCK-PadCFG2)") (class "Default")
      (node (ref "IC18") (pin "CFG2") (pinfunction "CFG2/SCK_CFG2") (pintype "bidirectional"))
    )
    (net (code "86") (name "unconnected-(IC18-CFG3{slash}CS-PadCFG3)") (class "Default")
      (node (ref "IC18") (pin "CFG3") (pinfunction "CFG3/CS_CFG3") (pintype "bidirectional"))
    )
    (net (code "87") (name "unconnected-(IC18-EN(CFG6)-PadEN)") (class "Default")
      (node (ref "IC18") (pin "EN") (pinfunction "EN(CFG6)_EN") (pintype "bidirectional"))
    )
    (net (code "88") (name "unconnected-(IC18-PadDIAG0)") (class "Default")
      (node (ref "IC18") (pin "DIAG0") (pinfunction "DIAG0_DIAG0") (pintype "bidirectional"))
    )
    (net (code "89") (name "unconnected-(IC18-PadDIAG1)") (class "Default")
      (node (ref "IC18") (pin "DIAG1") (pinfunction "DIAG1_DIAG1") (pintype "bidirectional"))
    )
    (net (code "90") (name "unconnected-(IC18-PadDIR)") (class "Default")
      (node (ref "IC18") (pin "DIR") (pinfunction "DIR_DIR") (pintype "bidirectional"))
    )
    (net (code "91") (name "unconnected-(IC18-PadSTEP)") (class "Default")
      (node (ref "IC18") (pin "STEP") (pinfunction "STEP_STEP") (pintype "bidirectional"))
    )
    (net (code "92") (name "unconnected-(IC18-PadVREF)") (class "Default")
      (node (ref "IC18") (pin "VREF") (pinfunction "VREF_VREF") (pintype "passive"))
    )
  )
)
